# Voltage_Translator.net
KiCad netlist of a schematic drawn in Altium Designer
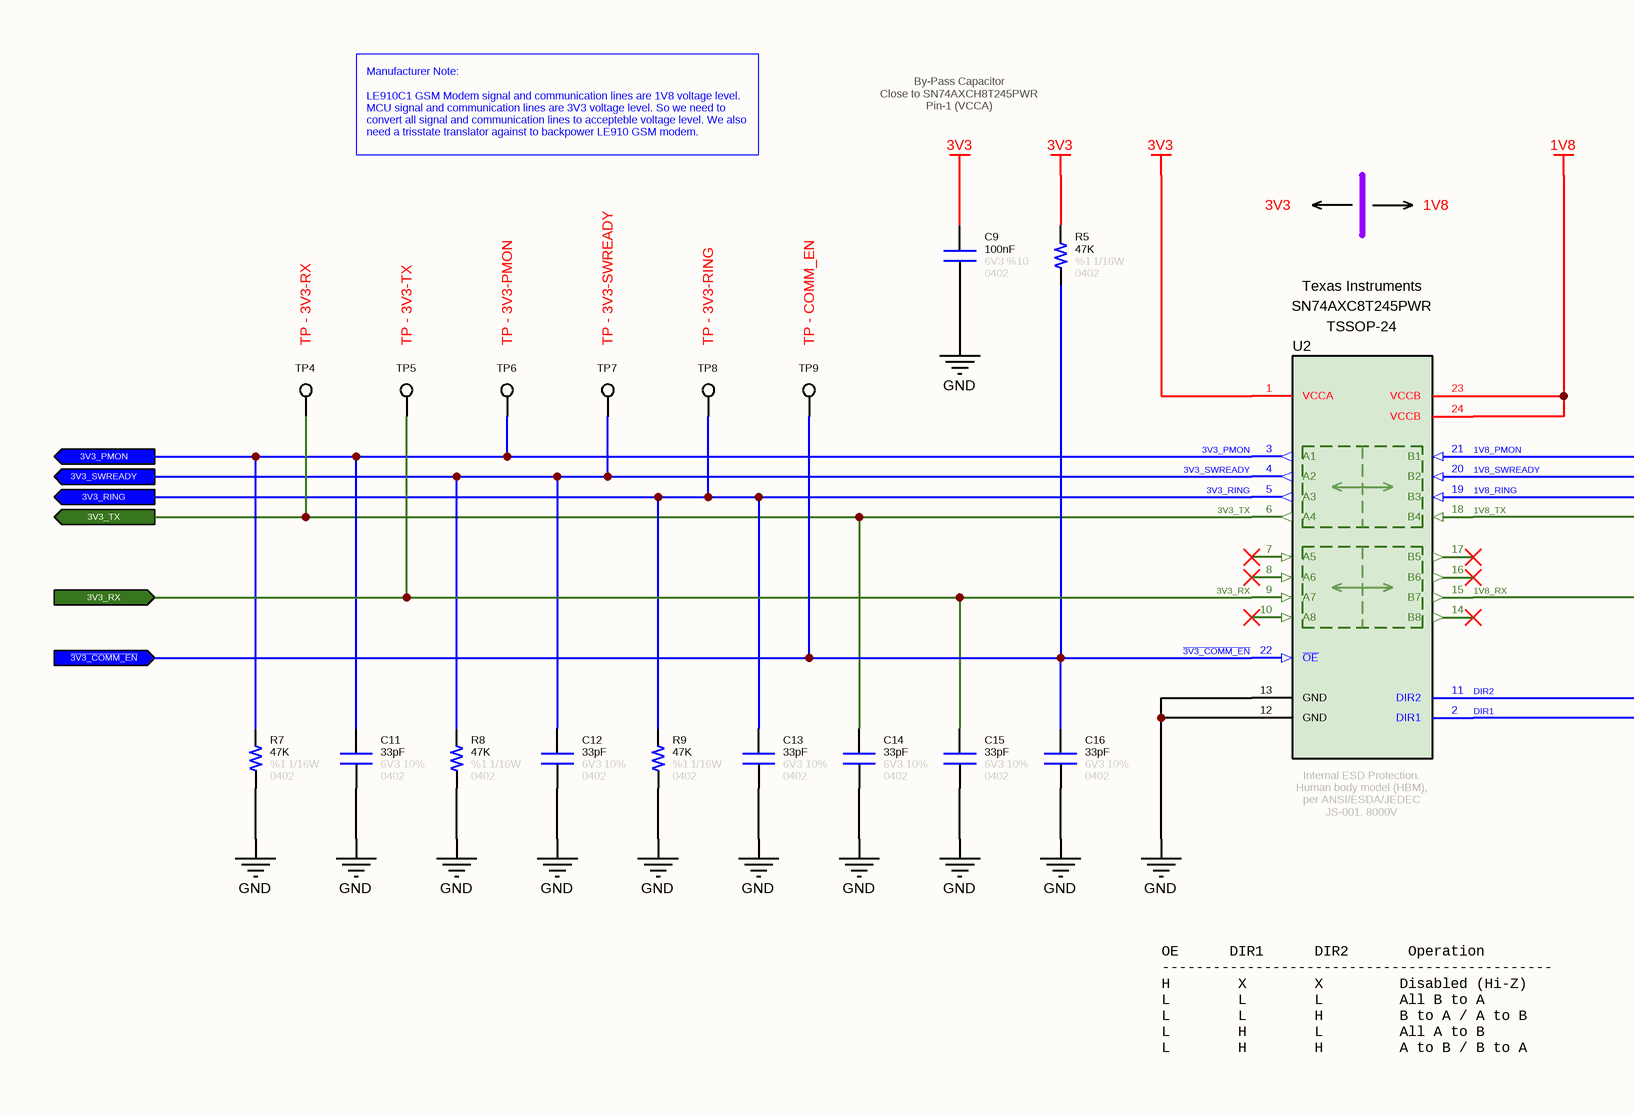
[diagram p0: Voltage_Translator.SchDoc, left]
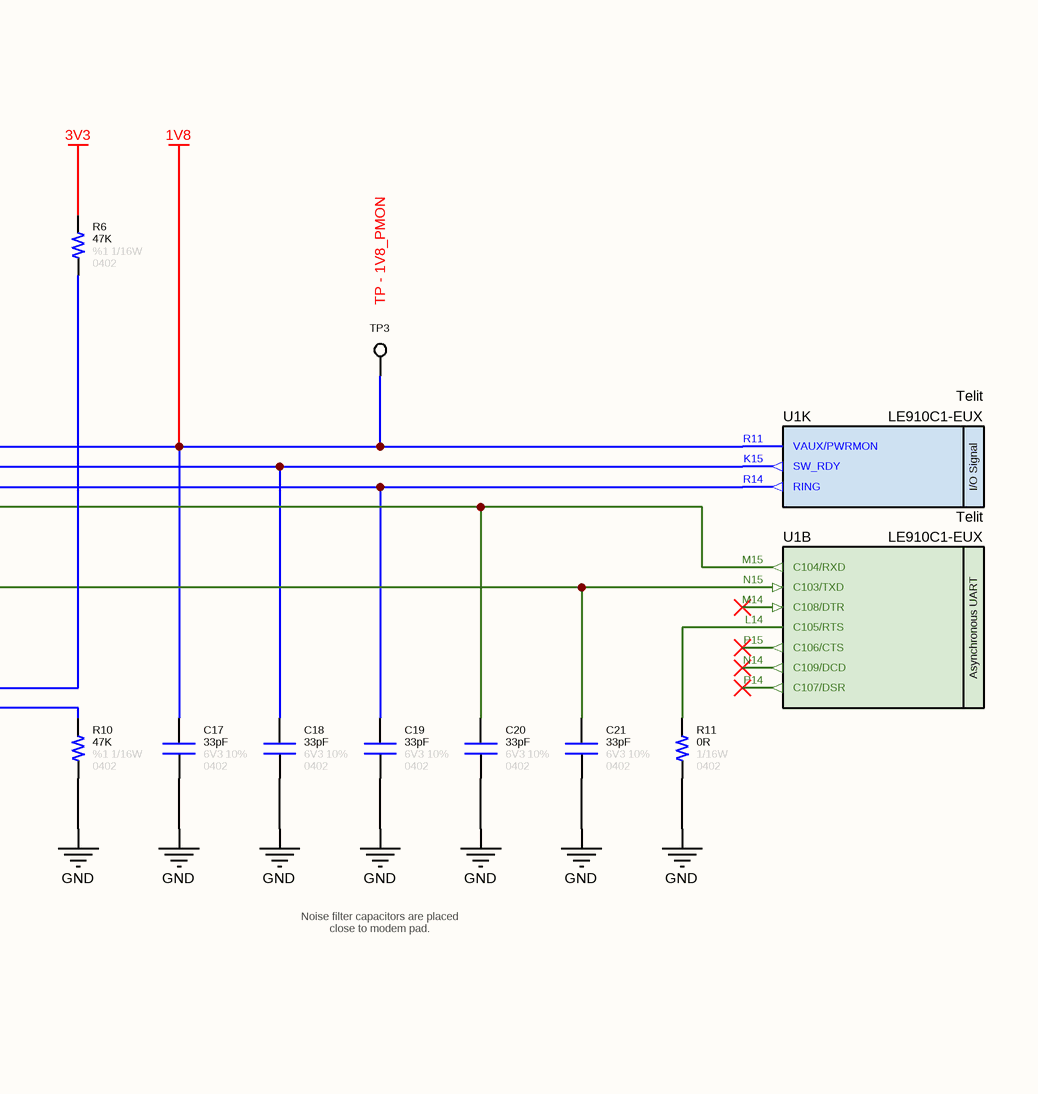
[diagram p1: Voltage_Translator.SchDoc, right]

(export (version "E")
  (design (tool "Eeschema 10.0.6"))
  (components
    (comp (ref "C9")
      (value "100nF")
      (footprint "CAPACITOR_0402")
      (description "Capacitor - 100nF [0402-6V3] (Ceramic)")
      (fields
        (field (name "MANUFACTURER PART NUMBER") "04026D104KAT4A")
        (field (name "TOLERANCE") "%10")
        (field (name "VOLTAGE") "6V3")
        (field (name "CASE") "0402")
        (field (name "Comment") "Capacitor - 100nF [0402] (Ceramic)")
      )
      (libsource (lib "Akkoyun") (part "Capacitor - 100nF [0402-6V3]"))
    )
    (comp (ref "C11")
      (value "33pF")
      (footprint "CAPACITOR_0402")
      (description "Capacitor - 33pF [0402] (Ceramic)")
      (fields
        (field (name "MANUFACTURER PART NUMBER") "C0402C330J9RACAUTO")
        (field (name "TOLERANCE") "10%")
        (field (name "CASE") "0402")
        (field (name "VOLTAGE") "6V3")
      )
      (libsource (lib "Akkoyun") (part "Capacitor - 33pF [0402-6V3]"))
    )
    (comp (ref "C12")
      (value "33pF")
      (footprint "CAPACITOR_0402")
      (description "Capacitor - 33pF [0402] (Ceramic)")
      (fields
        (field (name "MANUFACTURER PART NUMBER") "C0402C330J9RACAUTO")
        (field (name "TOLERANCE") "10%")
        (field (name "CASE") "0402")
        (field (name "VOLTAGE") "6V3")
      )
      (libsource (lib "Akkoyun") (part "Capacitor - 33pF [0402-6V3]"))
    )
    (comp (ref "C13")
      (value "33pF")
      (footprint "CAPACITOR_0402")
      (description "Capacitor - 33pF [0402] (Ceramic)")
      (fields
        (field (name "MANUFACTURER PART NUMBER") "C0402C330J9RACAUTO")
        (field (name "TOLERANCE") "10%")
        (field (name "CASE") "0402")
        (field (name "VOLTAGE") "6V3")
      )
      (libsource (lib "Akkoyun") (part "Capacitor - 33pF [0402-6V3]"))
    )
    (comp (ref "C14")
      (value "33pF")
      (footprint "CAPACITOR_0402")
      (description "Capacitor - 33pF [0402] (Ceramic)")
      (fields
        (field (name "MANUFACTURER PART NUMBER") "C0402C330J9RACAUTO")
        (field (name "TOLERANCE") "10%")
        (field (name "CASE") "0402")
        (field (name "VOLTAGE") "6V3")
      )
      (libsource (lib "Akkoyun") (part "Capacitor - 33pF [0402-6V3]"))
    )
    (comp (ref "C15")
      (value "33pF")
      (footprint "CAPACITOR_0402")
      (description "Capacitor - 33pF [0402] (Ceramic)")
      (fields
        (field (name "MANUFACTURER PART NUMBER") "C0402C330J9RACAUTO")
        (field (name "TOLERANCE") "10%")
        (field (name "CASE") "0402")
        (field (name "VOLTAGE") "6V3")
      )
      (libsource (lib "Akkoyun") (part "Capacitor - 33pF [0402-6V3]"))
    )
    (comp (ref "C16")
      (value "33pF")
      (footprint "CAPACITOR_0402")
      (description "Capacitor - 33pF [0402] (Ceramic)")
      (fields
        (field (name "MANUFACTURER PART NUMBER") "C0402C330J9RACAUTO")
        (field (name "TOLERANCE") "10%")
        (field (name "CASE") "0402")
        (field (name "VOLTAGE") "6V3")
      )
      (libsource (lib "Akkoyun") (part "Capacitor - 33pF [0402-6V3]"))
    )
    (comp (ref "C17")
      (value "33pF")
      (footprint "CAPACITOR_0402")
      (description "Capacitor - 33pF [0402] (Ceramic)")
      (fields
        (field (name "MANUFACTURER PART NUMBER") "C0402C330J9RACAUTO")
        (field (name "TOLERANCE") "10%")
        (field (name "CASE") "0402")
        (field (name "VOLTAGE") "6V3")
      )
      (libsource (lib "Akkoyun") (part "Capacitor - 33pF [0402-6V3]"))
    )
    (comp (ref "C18")
      (value "33pF")
      (footprint "CAPACITOR_0402")
      (description "Capacitor - 33pF [0402] (Ceramic)")
      (fields
        (field (name "MANUFACTURER PART NUMBER") "C0402C330J9RACAUTO")
        (field (name "TOLERANCE") "10%")
        (field (name "CASE") "0402")
        (field (name "VOLTAGE") "6V3")
      )
      (libsource (lib "Akkoyun") (part "Capacitor - 33pF [0402-6V3]"))
    )
    (comp (ref "C19")
      (value "33pF")
      (footprint "CAPACITOR_0402")
      (description "Capacitor - 33pF [0402] (Ceramic)")
      (fields
        (field (name "MANUFACTURER PART NUMBER") "C0402C330J9RACAUTO")
        (field (name "TOLERANCE") "10%")
        (field (name "CASE") "0402")
        (field (name "VOLTAGE") "6V3")
      )
      (libsource (lib "Akkoyun") (part "Capacitor - 33pF [0402-6V3]"))
    )
    (comp (ref "C20")
      (value "33pF")
      (footprint "CAPACITOR_0402")
      (description "Capacitor - 33pF [0402] (Ceramic)")
      (fields
        (field (name "MANUFACTURER PART NUMBER") "C0402C330J9RACAUTO")
        (field (name "TOLERANCE") "10%")
        (field (name "CASE") "0402")
        (field (name "VOLTAGE") "6V3")
      )
      (libsource (lib "Akkoyun") (part "Capacitor - 33pF [0402-6V3]"))
    )
    (comp (ref "C21")
      (value "33pF")
      (footprint "CAPACITOR_0402")
      (description "Capacitor - 33pF [0402] (Ceramic)")
      (fields
        (field (name "MANUFACTURER PART NUMBER") "C0402C330J9RACAUTO")
        (field (name "TOLERANCE") "10%")
        (field (name "CASE") "0402")
        (field (name "VOLTAGE") "6V3")
      )
      (libsource (lib "Akkoyun") (part "Capacitor - 33pF [0402-6V3]"))
    )
    (comp (ref "R5")
      (value "47K")
      (footprint "RESISTOR_0402")
      (description "Thick Film Resistors - SMD 1/16 W 47 KOhm 1%")
      (fields
        (field (name "MANUFACTURER PART NUMBER") "CRCW040247K0FKED")
        (field (name "TOLERANCE") "%1")
        (field (name "CASE") "0402")
        (field (name "POWER") "1/16W")
        (field (name "Comment") "47K - 0402 - %1 - 1/16W")
      )
      (libsource (lib "Akkoyun") (part "Resistor - 47K [0402]"))
    )
    (comp (ref "R6")
      (value "47K")
      (footprint "RESISTOR_0402")
      (description "Thick Film Resistors - SMD 1/16 W 47 KOhm 1%")
      (fields
        (field (name "MANUFACTURER PART NUMBER") "CRCW040247K0FKED")
        (field (name "TOLERANCE") "%1")
        (field (name "CASE") "0402")
        (field (name "POWER") "1/16W")
        (field (name "Comment") "47K - 0402 - %1 - 1/16W")
      )
      (libsource (lib "Akkoyun") (part "Resistor - 47K [0402]"))
    )
    (comp (ref "R7")
      (value "47K")
      (footprint "RESISTOR_0402")
      (description "Thick Film Resistors - SMD 1/16 W 47 KOhm 1%")
      (fields
        (field (name "MANUFACTURER PART NUMBER") "CRCW040247K0FKED")
        (field (name "TOLERANCE") "%1")
        (field (name "CASE") "0402")
        (field (name "POWER") "1/16W")
        (field (name "Comment") "47K - 0402 - %1 - 1/16W")
      )
      (libsource (lib "Akkoyun") (part "Resistor - 47K [0402]"))
    )
    (comp (ref "R8")
      (value "47K")
      (footprint "RESISTOR_0402")
      (description "Thick Film Resistors - SMD 1/16 W 47 KOhm 1%")
      (fields
        (field (name "MANUFACTURER PART NUMBER") "CRCW040247K0FKED")
        (field (name "TOLERANCE") "%1")
        (field (name "CASE") "0402")
        (field (name "POWER") "1/16W")
        (field (name "Comment") "47K - 0402 - %1 - 1/16W")
      )
      (libsource (lib "Akkoyun") (part "Resistor - 47K [0402]"))
    )
    (comp (ref "R9")
      (value "47K")
      (footprint "RESISTOR_0402")
      (description "Thick Film Resistors - SMD 1/16 W 47 KOhm 1%")
      (fields
        (field (name "MANUFACTURER PART NUMBER") "CRCW040247K0FKED")
        (field (name "TOLERANCE") "%1")
        (field (name "CASE") "0402")
        (field (name "POWER") "1/16W")
        (field (name "Comment") "47K - 0402 - %1 - 1/16W")
      )
      (libsource (lib "Akkoyun") (part "Resistor - 47K [0402]"))
    )
    (comp (ref "R10")
      (value "47K")
      (footprint "RESISTOR_0402")
      (description "Thick Film Resistors - SMD 1/16 W 47 KOhm 1%")
      (fields
        (field (name "MANUFACTURER PART NUMBER") "CRCW040247K0FKED")
        (field (name "TOLERANCE") "%1")
        (field (name "CASE") "0402")
        (field (name "POWER") "1/16W")
        (field (name "Comment") "47K - 0402 - %1 - 1/16W")
      )
      (libsource (lib "Akkoyun") (part "Resistor - 47K [0402]"))
    )
    (comp (ref "R11")
      (value "0R")
      (footprint "RESISTOR_0402")
      (description "Thick Film Resistors - SMD 1/16 W 0 Ohm")
      (fields
        (field (name "MANUFACTURER PART NUMBER") "CRCW04020000Z0ED")
        (field (name "CASE") "0402")
        (field (name "POWER") "1/16W")
        (field (name "Comment") "0R - 0402 - %1 - 1/16W")
      )
      (libsource (lib "Akkoyun") (part "Resistor - 0R [0402]"))
    )
    (comp (ref "TP3")
      (value "TP - 1V8_PMON")
      (footprint "TP")
      (description "Test Point")
      (libsource (lib "Akkoyun") (part "PCB - Test Point"))
    )
    (comp (ref "TP4")
      (value "TP - 3V3-RX")
      (footprint "TP")
      (description "Test Point")
      (libsource (lib "Akkoyun") (part "PCB - Test Point"))
    )
    (comp (ref "TP5")
      (value "TP - 3V3-TX")
      (footprint "TP")
      (description "Test Point")
      (libsource (lib "Akkoyun") (part "PCB - Test Point"))
    )
    (comp (ref "TP6")
      (value "TP - 3V3-PMON")
      (footprint "TP")
      (description "Test Point")
      (libsource (lib "Akkoyun") (part "PCB - Test Point"))
    )
    (comp (ref "TP7")
      (value "TP - 3V3-SWREADY")
      (footprint "TP")
      (description "Test Point")
      (libsource (lib "Akkoyun") (part "PCB - Test Point"))
    )
    (comp (ref "TP8")
      (value "TP - 3V3-RING")
      (footprint "TP")
      (description "Test Point")
      (libsource (lib "Akkoyun") (part "PCB - Test Point"))
    )
    (comp (ref "TP9")
      (value "TP - COMM_EN")
      (footprint "TP")
      (description "Test Point")
      (libsource (lib "Akkoyun") (part "PCB - Test Point"))
    )
    (comp (ref "U1")
      (value "LE910C1-EUX LTE GSM Module")
      (footprint "LE910 GSM Modem")
      (description "Telit LE910C1-EUX LTE/2G GSM Module")
      (fields
        (field (name "MANUFACTURER PART NUMBER") "LE910C1-EUX")
        (field (name "MANUFACTURER NAME") "Telit")
      )
      (libsource (lib "Akkoyun") (part "IC - LE910C1-EUX"))
    )
    (comp (ref "U2")
      (value "SN74AXC8T245PWR")
      (footprint "TSSOP-24")
      (description "Translation - Voltage Levels 8-Bit Dual-Supply Bus Transceiver 24-TSSOP -40 to 125")
      (fields
        (field (name "MANUFACTURER NAME") "Texas Instruments")
        (field (name "MANUFACTURER PART NUMBER") "SN74AXC8T245PWR")
        (field (name "CASE") "TSSOP-24")
      )
      (libsource (lib "Akkoyun") (part "IC - SN74AXC8T245PWR"))
    )
  )
  (nets
    (net (code "1") (name "/1V8_RING") (class "Default")
      (node (ref "C19") (pin "2") (pinfunction "2_2") (pintype "passive"))
      (node (ref "U1") (pin "R14") (pinfunction "RING_R14") (pintype "output"))
      (node (ref "U2") (pin "19") (pinfunction "B3_19") (pintype "input"))
    )
    (net (code "2") (name "/1V8_RX") (class "Default")
      (node (ref "C21") (pin "2") (pinfunction "2_2") (pintype "passive"))
      (node (ref "U1") (pin "N15") (pinfunction "C103/TXD_N15") (pintype "input"))
      (node (ref "U2") (pin "15") (pinfunction "B7_15") (pintype "output"))
    )
    (net (code "3") (name "/1V8_SWREADY") (class "Default")
      (node (ref "C18") (pin "2") (pinfunction "2_2") (pintype "passive"))
      (node (ref "U1") (pin "K15") (pinfunction "SW_RDY_K15") (pintype "output"))
      (node (ref "U2") (pin "20") (pinfunction "B2_20") (pintype "input"))
    )
    (net (code "4") (name "/1V8_TX") (class "Default")
      (node (ref "C20") (pin "2") (pinfunction "2_2") (pintype "passive"))
      (node (ref "U1") (pin "M15") (pinfunction "C104/RXD_M15") (pintype "output"))
      (node (ref "U2") (pin "18") (pinfunction "B4_18") (pintype "input"))
    )
    (net (code "5") (name "/3V3_PMON") (class "Default")
      (node (ref "C11") (pin "2") (pinfunction "2_2") (pintype "passive"))
      (node (ref "R7") (pin "2") (pinfunction "2_2") (pintype "passive"))
      (node (ref "TP6") (pin "1") (pinfunction "1_1") (pintype "passive"))
      (node (ref "U2") (pin "3") (pinfunction "A1_3") (pintype "output"))
    )
    (net (code "6") (name "/3V3_RING") (class "Default")
      (node (ref "C13") (pin "2") (pinfunction "2_2") (pintype "passive"))
      (node (ref "R9") (pin "2") (pinfunction "2_2") (pintype "passive"))
      (node (ref "TP8") (pin "1") (pinfunction "1_1") (pintype "passive"))
      (node (ref "U2") (pin "5") (pinfunction "A3_5") (pintype "output"))
    )
    (net (code "7") (name "/3V3_RX") (class "Default")
      (node (ref "C15") (pin "2") (pinfunction "2_2") (pintype "passive"))
      (node (ref "TP5") (pin "1") (pinfunction "1_1") (pintype "passive"))
      (node (ref "U2") (pin "9") (pinfunction "A7_9") (pintype "input"))
    )
    (net (code "8") (name "/3V3_SWREADY") (class "Default")
      (node (ref "C12") (pin "2") (pinfunction "2_2") (pintype "passive"))
      (node (ref "R8") (pin "2") (pinfunction "2_2") (pintype "passive"))
      (node (ref "TP7") (pin "1") (pinfunction "1_1") (pintype "passive"))
      (node (ref "U2") (pin "4") (pinfunction "A2_4") (pintype "output"))
    )
    (net (code "9") (name "/3V3_TX") (class "Default")
      (node (ref "C14") (pin "2") (pinfunction "2_2") (pintype "passive"))
      (node (ref "TP4") (pin "1") (pinfunction "1_1") (pintype "passive"))
      (node (ref "U2") (pin "6") (pinfunction "A4_6") (pintype "output"))
    )
    (net (code "10") (name "/DIR1") (class "Default")
      (node (ref "R10") (pin "2") (pinfunction "2_2") (pintype "passive"))
      (node (ref "U2") (pin "2") (pinfunction "DIR1_2") (pintype "passive"))
    )
    (net (code "11") (name "/DIR2") (class "Default")
      (node (ref "R6") (pin "1") (pinfunction "1_1") (pintype "passive"))
      (node (ref "U2") (pin "11") (pinfunction "DIR2_11") (pintype "passive"))
    )
    (net (code "12") (name "/~{3V3_COMM_EN}") (class "Default")
      (node (ref "C16") (pin "2") (pinfunction "2_2") (pintype "passive"))
      (node (ref "R5") (pin "1") (pinfunction "1_1") (pintype "passive"))
      (node (ref "TP9") (pin "1") (pinfunction "1_1") (pintype "passive"))
      (node (ref "U2") (pin "22") (pinfunction "~{OE}_22") (pintype "input"))
    )
    (net (code "13") (name "1V8") (class "Default")
      (node (ref "C17") (pin "2") (pinfunction "2_2") (pintype "passive"))
      (node (ref "TP3") (pin "1") (pinfunction "1_1") (pintype "passive"))
      (node (ref "U1") (pin "R11") (pinfunction "VAUX/PWRMON_R11") (pintype "passive"))
      (node (ref "U2") (pin "21") (pinfunction "B1_21") (pintype "input"))
      (node (ref "U2") (pin "23") (pinfunction "VCCB_23") (pintype "power_in"))
      (node (ref "U2") (pin "24") (pinfunction "VCCB_24") (pintype "power_in"))
    )
    (net (code "14") (name "3V3") (class "Default")
      (node (ref "C9") (pin "2") (pinfunction "2_2") (pintype "passive"))
      (node (ref "R5") (pin "2") (pinfunction "2_2") (pintype "passive"))
      (node (ref "R6") (pin "2") (pinfunction "2_2") (pintype "passive"))
      (node (ref "U2") (pin "1") (pinfunction "VCCA_1") (pintype "power_in"))
    )
    (net (code "15") (name "GND") (class "Default")
      (node (ref "C11") (pin "1") (pinfunction "1_1") (pintype "passive"))
      (node (ref "C12") (pin "1") (pinfunction "1_1") (pintype "passive"))
      (node (ref "C13") (pin "1") (pinfunction "1_1") (pintype "passive"))
      (node (ref "C14") (pin "1") (pinfunction "1_1") (pintype "passive"))
      (node (ref "C15") (pin "1") (pinfunction "1_1") (pintype "passive"))
      (node (ref "C16") (pin "1") (pinfunction "1_1") (pintype "passive"))
      (node (ref "C17") (pin "1") (pinfunction "1_1") (pintype "passive"))
      (node (ref "C18") (pin "1") (pinfunction "1_1") (pintype "passive"))
      (node (ref "C19") (pin "1") (pinfunction "1_1") (pintype "passive"))
      (node (ref "C20") (pin "1") (pinfunction "1_1") (pintype "passive"))
      (node (ref "C21") (pin "1") (pinfunction "1_1") (pintype "passive"))
      (node (ref "C9") (pin "1") (pinfunction "1_1") (pintype "passive"))
      (node (ref "R10") (pin "1") (pinfunction "1_1") (pintype "passive"))
      (node (ref "R11") (pin "1") (pinfunction "1_1") (pintype "passive"))
      (node (ref "R7") (pin "1") (pinfunction "1_1") (pintype "passive"))
      (node (ref "R8") (pin "1") (pinfunction "1_1") (pintype "passive"))
      (node (ref "R9") (pin "1") (pinfunction "1_1") (pintype "passive"))
      (node (ref "U2") (pin "12") (pinfunction "GND_12") (pintype "power_in"))
      (node (ref "U2") (pin "13") (pinfunction "GND_13") (pintype "power_in"))
    )
    (net (code "16") (name "Net-(U1B-C105{slash}RTS)") (class "Default")
      (node (ref "R11") (pin "2") (pinfunction "2_2") (pintype "passive"))
      (node (ref "U1") (pin "L14") (pinfunction "C105/RTS_L14") (pintype "open_collector"))
    )
    (net (code "17") (name "unconnected-(U1B-C106{slash}CTS-PadP15)") (class "Default")
      (node (ref "U1") (pin "P15") (pinfunction "C106/CTS_P15") (pintype "output+no_connect"))
    )
    (net (code "18") (name "unconnected-(U1B-C107{slash}DSR-PadP14)") (class "Default")
      (node (ref "U1") (pin "P14") (pinfunction "C107/DSR_P14") (pintype "output+no_connect"))
    )
    (net (code "19") (name "unconnected-(U1B-C108{slash}DTR-PadM14)") (class "Default")
      (node (ref "U1") (pin "M14") (pinfunction "C108/DTR_M14") (pintype "input+no_connect"))
    )
    (net (code "20") (name "unconnected-(U1B-C109{slash}DCD-PadN14)") (class "Default")
      (node (ref "U1") (pin "N14") (pinfunction "C109/DCD_N14") (pintype "output+no_connect"))
    )
    (net (code "21") (name "unconnected-(U2-A5-Pad7)") (class "Default")
      (node (ref "U2") (pin "7") (pinfunction "A5_7") (pintype "input+no_connect"))
    )
    (net (code "22") (name "unconnected-(U2-A6-Pad8)") (class "Default")
      (node (ref "U2") (pin "8") (pinfunction "A6_8") (pintype "input+no_connect"))
    )
    (net (code "23") (name "unconnected-(U2-A8-Pad10)") (class "Default")
      (node (ref "U2") (pin "10") (pinfunction "A8_10") (pintype "input+no_connect"))
    )
    (net (code "24") (name "unconnected-(U2-B5-Pad17)") (class "Default")
      (node (ref "U2") (pin "17") (pinfunction "B5_17") (pintype "output+no_connect"))
    )
    (net (code "25") (name "unconnected-(U2-B6-Pad16)") (class "Default")
      (node (ref "U2") (pin "16") (pinfunction "B6_16") (pintype "output+no_connect"))
    )
    (net (code "26") (name "unconnected-(U2-B8-Pad14)") (class "Default")
      (node (ref "U2") (pin "14") (pinfunction "B8_14") (pintype "output+no_connect"))
    )
  )
)
